# Schematic.net
KiCad netlist of a schematic drawn in EAGLE
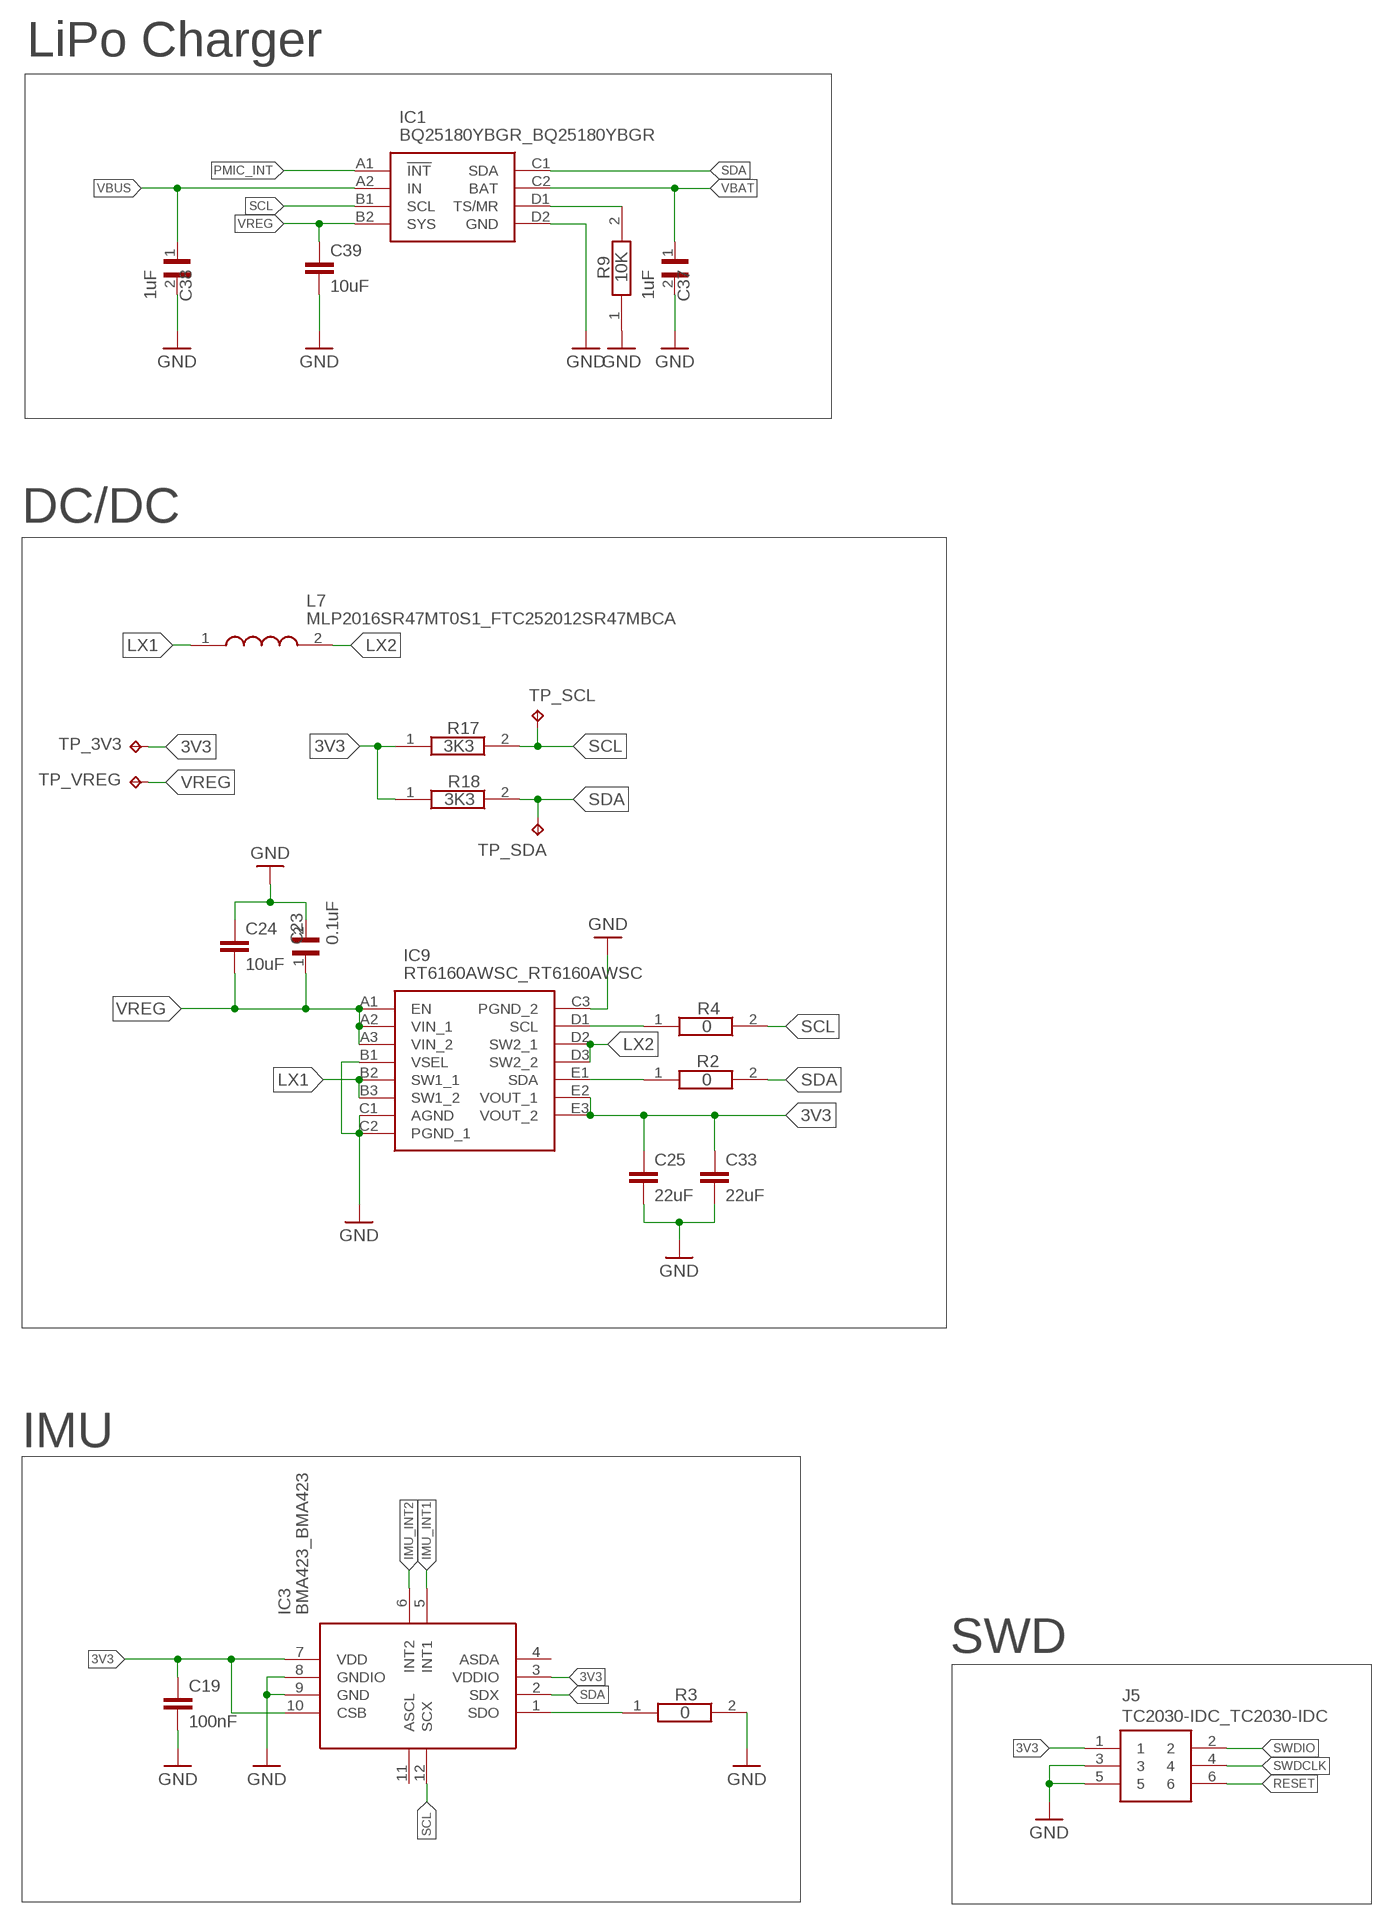
[diagram p0: schematic, sheet 1, part 1 of 3]
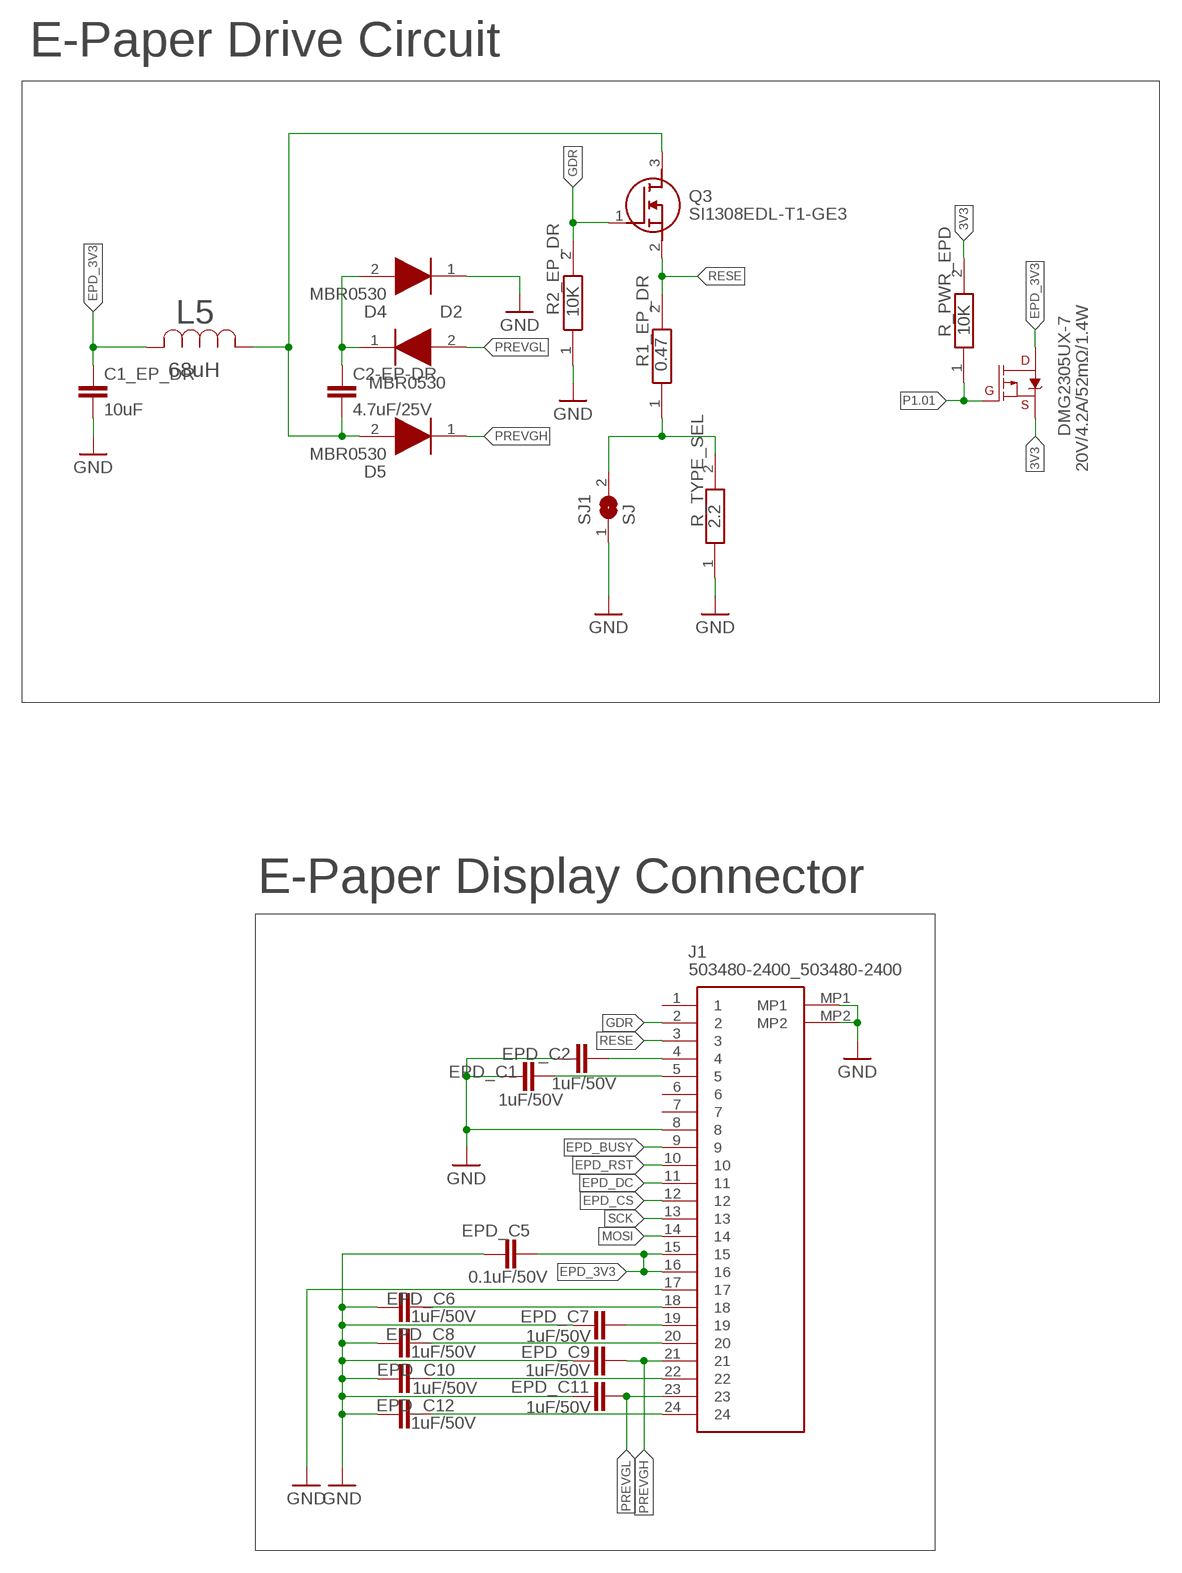
[diagram p1: schematic, sheet 1, part 2 of 3]
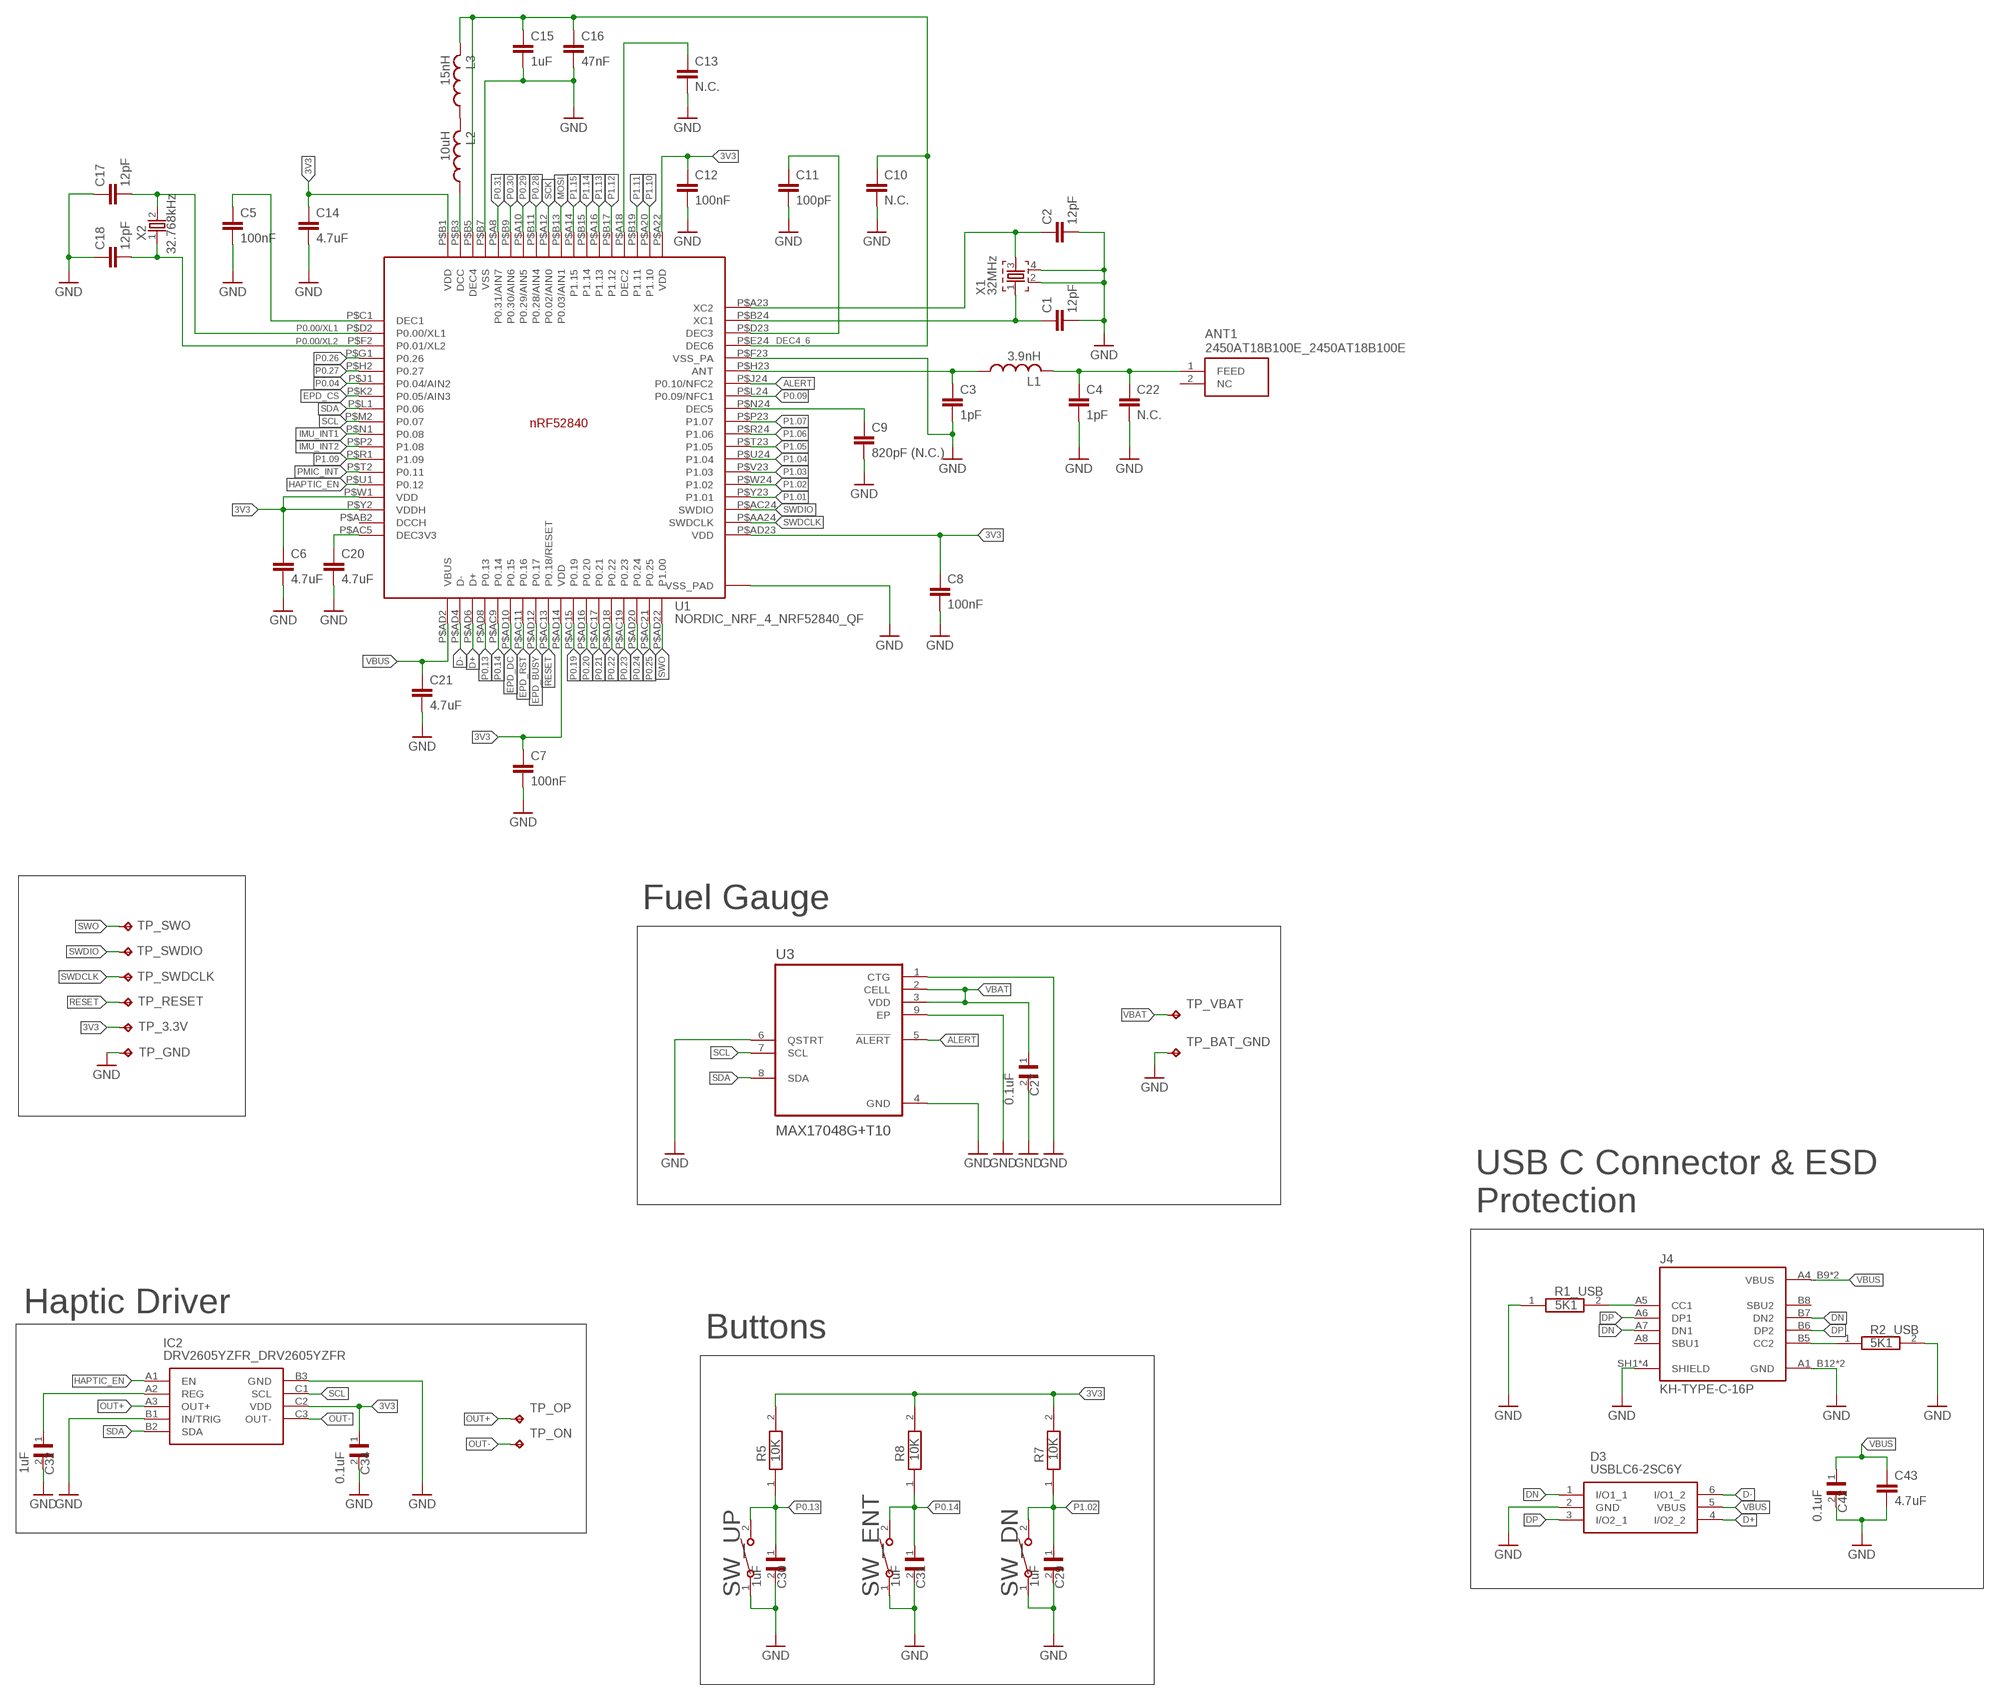
[diagram p2: schematic, sheet 1, part 3 of 3]

(export (version "E")
  (design (tool "Eeschema 10.0.6"))
  (components
    (comp (ref "ANT1")
      (value "2450AT18B100E_2450AT18B100E")
      (footprint "eagle-import:2450AT18B100E_ANTC3216X140N")
      (fields
        (field (name "ARROW_PART_NUMBER") "2450AT18B100E")
        (field (name "MOUSER_PART_NUMBER") "609-2450AT18B100E")
      )
      (libsource (lib "eagle-import") (part "2450AT18B100E_2450AT18B100E"))
    )
    (comp (ref "C1")
      (value "12pF")
      (footprint "eagle-import:NORDIC_NRF_3_RESC0201_L")
      (libsource (lib "eagle-import") (part "NORDIC_NRF_3_CAPACITOR_0201_L"))
    )
    (comp (ref "C1_EP_DR")
      (value "10uF")
      (footprint "eagle-import:NORDIC_NRF_3_RESC0402_L")
      (libsource (lib "eagle-import") (part "NORDIC_NRF_3_CAPACITOR_0402_L"))
    )
    (comp (ref "C2")
      (value "12pF")
      (footprint "eagle-import:NORDIC_NRF_3_RESC0201_L")
      (libsource (lib "eagle-import") (part "NORDIC_NRF_3_CAPACITOR_0201_L"))
    )
    (comp (ref "C2-EP-DR")
      (value "4.7uF/25V")
      (footprint "eagle-import:NORDIC_NRF_3_RESC0402_L")
      (libsource (lib "eagle-import") (part "NORDIC_NRF_3_CAPACITOR_0402_L"))
    )
    (comp (ref "C3")
      (value "1pF")
      (footprint "eagle-import:NORDIC_NRF_3_RESC0201_L")
      (libsource (lib "eagle-import") (part "NORDIC_NRF_3_CAPACITOR_0201_L"))
    )
    (comp (ref "C4")
      (value "1pF")
      (footprint "eagle-import:NORDIC_NRF_3_RESC0201_L")
      (libsource (lib "eagle-import") (part "NORDIC_NRF_3_CAPACITOR_0201_L"))
    )
    (comp (ref "C5")
      (value "100nF")
      (footprint "eagle-import:NORDIC_NRF_3_RESC0201_L")
      (libsource (lib "eagle-import") (part "NORDIC_NRF_3_CAPACITOR_0201_L"))
    )
    (comp (ref "C6")
      (value "4.7uF")
      (footprint "eagle-import:NORDIC_NRF_3_RESC0402_L")
      (libsource (lib "eagle-import") (part "NORDIC_NRF_3_CAPACITOR_0402_L"))
    )
    (comp (ref "C7")
      (value "100nF")
      (footprint "eagle-import:NORDIC_NRF_3_RESC0201_L")
      (libsource (lib "eagle-import") (part "NORDIC_NRF_3_CAPACITOR_0201_L"))
    )
    (comp (ref "C8")
      (value "100nF")
      (footprint "eagle-import:NORDIC_NRF_3_RESC0201_L")
      (libsource (lib "eagle-import") (part "NORDIC_NRF_3_CAPACITOR_0201_L"))
    )
    (comp (ref "C9")
      (value "820pF (N.C.)")
      (footprint "eagle-import:NORDIC_NRF_3_RESC0201_L")
      (libsource (lib "eagle-import") (part "NORDIC_NRF_3_CAPACITOR_0201_L"))
    )
    (comp (ref "C10")
      (value "N.C.")
      (footprint "eagle-import:NORDIC_NRF_3_RESC0201_L")
      (libsource (lib "eagle-import") (part "NORDIC_NRF_3_CAPACITOR_0201_L"))
    )
    (comp (ref "C11")
      (value "100pF")
      (footprint "eagle-import:NORDIC_NRF_3_RESC0201_L")
      (libsource (lib "eagle-import") (part "NORDIC_NRF_3_CAPACITOR_0201_L"))
    )
    (comp (ref "C12")
      (value "100nF")
      (footprint "eagle-import:NORDIC_NRF_3_RESC0201_L")
      (libsource (lib "eagle-import") (part "NORDIC_NRF_3_CAPACITOR_0201_L"))
    )
    (comp (ref "C13")
      (value "N.C.")
      (footprint "eagle-import:NORDIC_NRF_3_RESC0201_L")
      (libsource (lib "eagle-import") (part "NORDIC_NRF_3_CAPACITOR_0201_L"))
    )
    (comp (ref "C14")
      (value "4.7uF")
      (footprint "eagle-import:NORDIC_NRF_3_RESC0402_L")
      (libsource (lib "eagle-import") (part "NORDIC_NRF_3_CAPACITOR_0402_L"))
    )
    (comp (ref "C15")
      (value "1uF")
      (footprint "eagle-import:NORDIC_NRF_3_RESC0402_L")
      (libsource (lib "eagle-import") (part "NORDIC_NRF_3_CAPACITOR_0402_L"))
    )
    (comp (ref "C16")
      (value "47nF")
      (footprint "eagle-import:NORDIC_NRF_3_RESC0201_L")
      (libsource (lib "eagle-import") (part "NORDIC_NRF_3_CAPACITOR_0201_L"))
    )
    (comp (ref "C17")
      (value "12pF")
      (footprint "eagle-import:NORDIC_NRF_3_RESC0201_L")
      (libsource (lib "eagle-import") (part "NORDIC_NRF_3_CAPACITOR_0201_L"))
    )
    (comp (ref "C18")
      (value "12pF")
      (footprint "eagle-import:NORDIC_NRF_3_RESC0201_L")
      (libsource (lib "eagle-import") (part "NORDIC_NRF_3_CAPACITOR_0201_L"))
    )
    (comp (ref "C19")
      (value "100nF")
      (footprint "eagle-import:NORDIC_NRF_3_RESC0201_L")
      (libsource (lib "eagle-import") (part "NORDIC_NRF_3_CAPACITOR_0201_L"))
    )
    (comp (ref "C20")
      (value "4.7uF")
      (footprint "eagle-import:NORDIC_NRF_3_RESC0402_L")
      (libsource (lib "eagle-import") (part "NORDIC_NRF_3_CAPACITOR_0402_L"))
    )
    (comp (ref "C21")
      (value "4.7uF")
      (footprint "eagle-import:NORDIC_NRF_3_RESC0402_L")
      (libsource (lib "eagle-import") (part "NORDIC_NRF_3_CAPACITOR_0402_L"))
    )
    (comp (ref "C22")
      (value "N.C.")
      (footprint "eagle-import:NORDIC_NRF_3_RESC0201_L")
      (libsource (lib "eagle-import") (part "NORDIC_NRF_3_CAPACITOR_0201_L"))
    )
    (comp (ref "C23")
      (value "0.1uF")
      (footprint "eagle-import:GRM011R60J152KE01L_2_CAPC0201X13N")
      (fields (field (name "MF") "Murata") (field (name "MP") "GRM011R60J152KE01L"))
      (libsource (lib "eagle-import") (part "GRM011R60J152KE01L_2_GRM011R60J152KE01L"))
    )
    (comp (ref "C24")
      (value "10uF")
      (footprint "eagle-import:NORDIC_NRF_3_RESC0402_L")
      (libsource (lib "eagle-import") (part "NORDIC_NRF_3_CAPACITOR_0402_L"))
    )
    (comp (ref "C25")
      (value "22uF")
      (footprint "eagle-import:NORDIC_NRF_3_RESC0402_L")
      (libsource (lib "eagle-import") (part "NORDIC_NRF_3_CAPACITOR_0402_L"))
    )
    (comp (ref "C27")
      (value "0.1uF")
      (footprint "eagle-import:GRM011R60J152KE01L_2_CAPC0201X13N")
      (fields (field (name "MF") "Murata") (field (name "MP") "GRM011R60J152KE01L"))
      (libsource (lib "eagle-import") (part "GRM011R60J152KE01L_2_GRM011R60J152KE01L"))
    )
    (comp (ref "C29")
      (value "1uF")
      (footprint "eagle-import:GRM011R60J152KE01L_2_CAPC0201X13N")
      (fields (field (name "MF") "Murata") (field (name "MP") "GRM011R60J152KE01L"))
      (libsource (lib "eagle-import") (part "GRM011R60J152KE01L_2_GRM011R60J152KE01L"))
    )
    (comp (ref "C30")
      (value "1uF")
      (footprint "eagle-import:GRM011R60J152KE01L_2_CAPC0201X13N")
      (fields (field (name "MF") "Murata") (field (name "MP") "GRM011R60J152KE01L"))
      (libsource (lib "eagle-import") (part "GRM011R60J152KE01L_2_GRM011R60J152KE01L"))
    )
    (comp (ref "C31")
      (value "1uF")
      (footprint "eagle-import:GRM011R60J152KE01L_2_CAPC0201X13N")
      (fields (field (name "MF") "Murata") (field (name "MP") "GRM011R60J152KE01L"))
      (libsource (lib "eagle-import") (part "GRM011R60J152KE01L_2_GRM011R60J152KE01L"))
    )
    (comp (ref "C32")
      (value "1uF")
      (footprint "eagle-import:GRM011R60J152KE01L_2_CAPC0201X13N")
      (fields (field (name "MF") "Murata") (field (name "MP") "GRM011R60J152KE01L"))
      (libsource (lib "eagle-import") (part "GRM011R60J152KE01L_2_GRM011R60J152KE01L"))
    )
    (comp (ref "C33")
      (value "22uF")
      (footprint "eagle-import:NORDIC_NRF_3_RESC0402_L")
      (libsource (lib "eagle-import") (part "NORDIC_NRF_3_CAPACITOR_0402_L"))
    )
    (comp (ref "C34")
      (value "0.1uF")
      (footprint "eagle-import:GRM011R60J152KE01L_2_CAPC0201X13N")
      (fields (field (name "MF") "Murata") (field (name "MP") "GRM011R60J152KE01L"))
      (libsource (lib "eagle-import") (part "GRM011R60J152KE01L_2_GRM011R60J152KE01L"))
    )
    (comp (ref "C37")
      (value "1uF")
      (footprint "eagle-import:GRM011R60J152KE01L_2_CAPC0201X13N")
      (fields (field (name "MF") "Murata") (field (name "MP") "GRM011R60J152KE01L"))
      (libsource (lib "eagle-import") (part "GRM011R60J152KE01L_2_GRM011R60J152KE01L"))
    )
    (comp (ref "C38")
      (value "1uF")
      (footprint "eagle-import:GRM011R60J152KE01L_2_CAPC0201X13N")
      (fields (field (name "MF") "Murata") (field (name "MP") "GRM011R60J152KE01L"))
      (libsource (lib "eagle-import") (part "GRM011R60J152KE01L_2_GRM011R60J152KE01L"))
    )
    (comp (ref "C39")
      (value "10uF")
      (footprint "eagle-import:NORDIC_NRF_3_RESC0402_L")
      (libsource (lib "eagle-import") (part "NORDIC_NRF_3_CAPACITOR_0402_L"))
    )
    (comp (ref "C42")
      (value "0.1uF")
      (footprint "eagle-import:GRM011R60J152KE01L_2_CAPC0201X13N")
      (fields (field (name "MF") "Murata") (field (name "MP") "GRM011R60J152KE01L"))
      (libsource (lib "eagle-import") (part "GRM011R60J152KE01L_2_GRM011R60J152KE01L"))
    )
    (comp (ref "C43")
      (value "4.7uF")
      (footprint "eagle-import:NORDIC_NRF_3_RESC0402_L")
      (libsource (lib "eagle-import") (part "NORDIC_NRF_3_CAPACITOR_0402_L"))
    )
    (comp (ref "D2")
      (value "MBR0530")
      (footprint "eagle-import:ESP32_C6_LIBRARY_5_SOD3716X135N")
      (fields (field (name "MF") "ON Semiconductor"))
      (libsource (lib "eagle-import") (part "ESP32_C6_LIBRARY_5_MBR0530"))
    )
    (comp (ref "D3")
      (value "USBLC6-2SC6Y")
      (footprint "eagle-import:ESP32_C6_LIBRARY_3_SOT95P280X145-6N")
      (fields (field (name "MF") "STMicroelectronics"))
      (libsource (lib "eagle-import") (part "ESP32_C6_LIBRARY_3_USBLC6-2SC6Y"))
    )
    (comp (ref "D4")
      (value "MBR0530")
      (footprint "eagle-import:ESP32_C6_LIBRARY_5_SOD3716X135N")
      (fields (field (name "MF") "ON Semiconductor"))
      (libsource (lib "eagle-import") (part "ESP32_C6_LIBRARY_5_MBR0530"))
    )
    (comp (ref "D5")
      (value "MBR0530")
      (footprint "eagle-import:ESP32_C6_LIBRARY_5_SOD3716X135N")
      (fields (field (name "MF") "ON Semiconductor"))
      (libsource (lib "eagle-import") (part "ESP32_C6_LIBRARY_5_MBR0530"))
    )
    (comp (ref "DMG2305UX-7")
      (value "20V/4.2A/52mΩ/1.4W")
      (footprint "eagle-import:ESP32_C6_LIBRARY_4_ESP32_C6_LIBRARY_4_ESP32_C6_LIBRARY_4_ESP32_C6_LIBRARY_4_ESP32_WROVER_SPARKFUN-DISCRETESEMI_SOT23-3")
      (libsource (lib "eagle-import") (part "ESP32_C6_LIBRARY_4_ESP32_WROVER_SPARKFUN-DISCRETESEMI_MOSFET_PCH-DMG2305UX-7"))
    )
    (comp (ref "EPD_C1")
      (value "1uF/50V")
      (footprint "eagle-import:NORDIC_NRF_3_RESC0402_L")
      (libsource (lib "eagle-import") (part "NORDIC_NRF_3_CAPACITOR_0402_L"))
    )
    (comp (ref "EPD_C2")
      (value "1uF/50V")
      (footprint "eagle-import:NORDIC_NRF_3_RESC0402_L")
      (libsource (lib "eagle-import") (part "NORDIC_NRF_3_CAPACITOR_0402_L"))
    )
    (comp (ref "EPD_C5")
      (value "0.1uF/50V")
      (footprint "eagle-import:NORDIC_NRF_3_RESC0201_L")
      (libsource (lib "eagle-import") (part "NORDIC_NRF_3_CAPACITOR_0201_L"))
    )
    (comp (ref "EPD_C6")
      (value "1uF/50V")
      (footprint "eagle-import:NORDIC_NRF_3_RESC0402_L")
      (libsource (lib "eagle-import") (part "NORDIC_NRF_3_CAPACITOR_0402_L"))
    )
    (comp (ref "EPD_C7")
      (value "1uF/50V")
      (footprint "eagle-import:NORDIC_NRF_3_RESC0402_L")
      (libsource (lib "eagle-import") (part "NORDIC_NRF_3_CAPACITOR_0402_L"))
    )
    (comp (ref "EPD_C8")
      (value "1uF/50V")
      (footprint "eagle-import:NORDIC_NRF_3_RESC0402_L")
      (libsource (lib "eagle-import") (part "NORDIC_NRF_3_CAPACITOR_0402_L"))
    )
    (comp (ref "EPD_C9")
      (value "1uF/50V")
      (footprint "eagle-import:NORDIC_NRF_3_RESC0402_L")
      (libsource (lib "eagle-import") (part "NORDIC_NRF_3_CAPACITOR_0402_L"))
    )
    (comp (ref "EPD_C10")
      (value "1uF/50V")
      (footprint "eagle-import:NORDIC_NRF_3_RESC0402_L")
      (libsource (lib "eagle-import") (part "NORDIC_NRF_3_CAPACITOR_0402_L"))
    )
    (comp (ref "EPD_C11")
      (value "1uF/50V")
      (footprint "eagle-import:NORDIC_NRF_3_RESC0402_L")
      (libsource (lib "eagle-import") (part "NORDIC_NRF_3_CAPACITOR_0402_L"))
    )
    (comp (ref "EPD_C12")
      (value "1uF/50V")
      (footprint "eagle-import:NORDIC_NRF_3_RESC0402_L")
      (libsource (lib "eagle-import") (part "NORDIC_NRF_3_CAPACITOR_0402_L"))
    )
    (comp (ref "IC1")
      (value "BQ25180YBGR_BQ25180YBGR")
      (footprint "eagle-import:BQ25180YBGR_BGA8C40P2X4_100X155X50")
      (fields
        (field (name "ARROW_PART_NUMBER") "BQ25180YBGR")
        (field (name "MOUSER_PART_NUMBER") "595-BQ25180YBGR")
      )
      (libsource (lib "eagle-import") (part "BQ25180YBGR_BQ25180YBGR"))
    )
    (comp (ref "IC2")
      (value "DRV2605YZFR_DRV2605YZFR")
      (footprint "eagle-import:DRV2605YZFR_BGA9C50P3X3_144X144X62")
      (fields (field (name "ARROW_PART_NUMBER") "DRV2605YZFR"))
      (libsource (lib "eagle-import") (part "DRV2605YZFR_DRV2605YZFR"))
    )
    (comp (ref "IC3")
      (value "BMA423_BMA423")
      (footprint "eagle-import:BMA423_BMA423")
      (fields (field (name "ARROW_PART_NUMBER") "BMA423") (field (name "MOUSER_PART_NUMBER") "262-BMA423"))
      (libsource (lib "eagle-import") (part "BMA423_BMA423"))
    )
    (comp (ref "IC9")
      (value "RT6160AWSC_RT6160AWSC")
      (footprint "eagle-import:RT6160AWSC_BGA15C40P3X5_140X230X60")
      (fields
        (field (name "MANUFACTURER_PART_NUMBER") "RT6160AWSC")
        (field (name "MOUSER_PART_NUMBER") "835-RT6160AWSC")
      )
      (libsource (lib "eagle-import") (part "RT6160AWSC_RT6160AWSC"))
    )
    (comp (ref "J1")
      (value "503480-2400_503480-2400")
      (footprint "eagle-import:503480-2400_5034802400")
      (fields
        (field (name "MANUFACTURER_PART_NUMBER") "503480-2400")
        (field (name "MOUSER_PART_NUMBER") "538-503480-2400")
      )
      (libsource (lib "eagle-import") (part "503480-2400_503480-2400"))
    )
    (comp (ref "J4")
      (value "KH-TYPE-C-16P")
      (footprint "eagle-import:KH-TYPE-C-16P_KINGHELM_KH-TYPE-C-16P")
      (fields (field (name "MF") "kinghelm"))
      (libsource (lib "eagle-import") (part "KH-TYPE-C-16P_KH-TYPE-C-16P"))
    )
    (comp (ref "J5")
      (value "TC2030-IDC_TC2030-IDC")
      (footprint "eagle-import:TC2030-IDC_TC2030IDC")
      (fields (field (name "MANUFACTURER_PART_NUMBER") "TC2030-IDC"))
      (libsource (lib "eagle-import") (part "TC2030-IDC_TC2030-IDC"))
    )
    (comp (ref "L1")
      (value "3.9nH")
      (footprint "eagle-import:NORDIC_NRF_2_RESC0201_L")
      (libsource (lib "eagle-import") (part "NORDIC_NRF_2_INDUCTOR_0201_L"))
    )
    (comp (ref "L2")
      (value "10uH")
      (footprint "eagle-import:NORDIC_NRF_2_RESC0402_L")
      (libsource (lib "eagle-import") (part "NORDIC_NRF_2_INDUCTOR_0402_L"))
    )
    (comp (ref "L3")
      (value "15nH")
      (footprint "eagle-import:NORDIC_NRF_2_RESC0201_L")
      (libsource (lib "eagle-import") (part "NORDIC_NRF_2_INDUCTOR_0201_L"))
    )
    (comp (ref "L5")
      (value "68uH")
      (footprint "eagle-import:ESP32_C6_LIBRARY_2_IND_4828-WE-TPC_WRE")
      (fields
        (field (name "MANUFACTURER_PART_NUMBER") "744043680")
        (field (name "COPYRIGHT") "Copyright (C) 2024 Ultra Librarian. All rights reserved.")
      )
      (libsource (lib "eagle-import") (part "ESP32_C6_LIBRARY_2_744043680IND_4828-WE-TPC_WRE"))
    )
    (comp (ref "L7")
      (value "MLP2016SR47MT0S1_FTC252012SR47MBCA")
      (footprint "eagle-import:MLP2016SR47MT0S1_INDC2016X100N")
      (fields (field (name "MANUFACTURER_PART_NUMBER") "FTC252012SR47MBCA"))
      (libsource (lib "eagle-import") (part "MLP2016SR47MT0S1_FTC252012SR47MBCA"))
    )
    (comp (ref "Q3")
      (value "SI1308EDL-T1-GE3")
      (footprint "eagle-import:ESP32_C6_LIBRARY_6_SOT65P210X110-3N")
      (fields (field (name "MF") "Vishay Siliconix"))
      (libsource (lib "eagle-import") (part "ESP32_C6_LIBRARY_6_SI1308EDL-T1-GE3"))
    )
    (comp (ref "R1_EP_DR")
      (value "0.47")
      (footprint "eagle-import:CPF0201D7K68C1_0201")
      (libsource (lib "eagle-import") (part "CPF0201D7K68C1_CPF0201D7K68C1"))
    )
    (comp (ref "R1_USB")
      (value "5K1")
      (footprint "eagle-import:CPF0201D7K68C1_0201")
      (libsource (lib "eagle-import") (part "CPF0201D7K68C1_CPF0201D7K68C1"))
    )
    (comp (ref "R2")
      (value "0")
      (footprint "eagle-import:CPF0201D7K68C1_0201")
      (libsource (lib "eagle-import") (part "CPF0201D7K68C1_CPF0201D7K68C1"))
    )
    (comp (ref "R2_EP_DR")
      (value "10K")
      (footprint "eagle-import:CPF0201D7K68C1_0201")
      (libsource (lib "eagle-import") (part "CPF0201D7K68C1_CPF0201D7K68C1"))
    )
    (comp (ref "R2_USB")
      (value "5K1")
      (footprint "eagle-import:CPF0201D7K68C1_0201")
      (libsource (lib "eagle-import") (part "CPF0201D7K68C1_CPF0201D7K68C1"))
    )
    (comp (ref "R3")
      (value "0")
      (footprint "eagle-import:CPF0201D7K68C1_0201")
      (libsource (lib "eagle-import") (part "CPF0201D7K68C1_CPF0201D7K68C1"))
    )
    (comp (ref "R4")
      (value "0")
      (footprint "eagle-import:CPF0201D7K68C1_0201")
      (libsource (lib "eagle-import") (part "CPF0201D7K68C1_CPF0201D7K68C1"))
    )
    (comp (ref "R5")
      (value "10K")
      (footprint "eagle-import:CPF0201D7K68C1_0201")
      (libsource (lib "eagle-import") (part "CPF0201D7K68C1_CPF0201D7K68C1"))
    )
    (comp (ref "R7")
      (value "10K")
      (footprint "eagle-import:CPF0201D7K68C1_0201")
      (libsource (lib "eagle-import") (part "CPF0201D7K68C1_CPF0201D7K68C1"))
    )
    (comp (ref "R8")
      (value "10K")
      (footprint "eagle-import:CPF0201D7K68C1_0201")
      (libsource (lib "eagle-import") (part "CPF0201D7K68C1_CPF0201D7K68C1"))
    )
    (comp (ref "R9")
      (value "10K")
      (footprint "eagle-import:CPF0201D7K68C1_0201")
      (libsource (lib "eagle-import") (part "CPF0201D7K68C1_CPF0201D7K68C1"))
    )
    (comp (ref "R17")
      (value "3K3")
      (footprint "eagle-import:CPF0201D7K68C1_0201")
      (libsource (lib "eagle-import") (part "CPF0201D7K68C1_CPF0201D7K68C1"))
    )
    (comp (ref "R18")
      (value "3K3")
      (footprint "eagle-import:CPF0201D7K68C1_0201")
      (libsource (lib "eagle-import") (part "CPF0201D7K68C1_CPF0201D7K68C1"))
    )
    (comp (ref "R_PWR_EPD")
      (value "10K")
      (footprint "eagle-import:CPF0201D7K68C1_0201")
      (libsource (lib "eagle-import") (part "CPF0201D7K68C1_CPF0201D7K68C1"))
    )
    (comp (ref "R_TYPE_SEL")
      (value "2.2")
      (footprint "eagle-import:CPF0201D7K68C1_0201")
      (libsource (lib "eagle-import") (part "CPF0201D7K68C1_CPF0201D7K68C1"))
    )
    (comp (ref "SJ1")
      (value "SJ")
      (footprint "eagle-import:ESP32_C6_LIBRARY_7_JUMPER_SJ")
      (libsource (lib "eagle-import") (part "ESP32_C6_LIBRARY_7_JUMPER_SJ"))
    )
    (comp (ref "SW_DN")
      (value "2025-10-22_07-23-44_LIBRARY_EVP-AKE31ASW_EVP-AKE31A_PAN")
      (footprint "eagle-import:2025-10-22_07-23-44_LIBRARY_SW_EVP-AKE31A_PAN")
      (fields
        (field (name "MANUFACTURER_PART_NUMBER") "EVP-AKE31A")
        (field (name "COPYRIGHT") "Copyright (C) 2025 Ultra Librarian. All rights reserved.")
      )
      (libsource (lib "eagle-import") (part "2025-10-22_07-23-44_LIBRARY_EVP-AKE31ASW_EVP-AKE31A_PAN"))
    )
    (comp (ref "SW_ENT")
      (value "2025-10-22_07-23-44_LIBRARY_EVP-AKE31ASW_EVP-AKE31A_PAN")
      (footprint "eagle-import:2025-10-22_07-23-44_LIBRARY_SW_EVP-AKE31A_PAN")
      (fields
        (field (name "MANUFACTURER_PART_NUMBER") "EVP-AKE31A")
        (field (name "COPYRIGHT") "Copyright (C) 2025 Ultra Librarian. All rights reserved.")
      )
      (libsource (lib "eagle-import") (part "2025-10-22_07-23-44_LIBRARY_EVP-AKE31ASW_EVP-AKE31A_PAN"))
    )
    (comp (ref "SW_UP")
      (value "2025-10-22_07-23-44_LIBRARY_EVP-AKE31ASW_EVP-AKE31A_PAN")
      (footprint "eagle-import:2025-10-22_07-23-44_LIBRARY_SW_EVP-AKE31A_PAN")
      (fields
        (field (name "MANUFACTURER_PART_NUMBER") "EVP-AKE31A")
        (field (name "COPYRIGHT") "Copyright (C) 2025 Ultra Librarian. All rights reserved.")
      )
      (libsource (lib "eagle-import") (part "2025-10-22_07-23-44_LIBRARY_EVP-AKE31ASW_EVP-AKE31A_PAN"))
    )
    (comp (ref "TP_3.3V")
      (value "HECTOR_WATCH_1_TPTP20R")
      (footprint "eagle-import:HECTOR_WATCH_1_TP20R")
      (libsource (lib "eagle-import") (part "HECTOR_WATCH_1_TPTP20R"))
    )
    (comp (ref "TP_3V3")
      (value "HECTOR_WATCH_1_TPTP20R")
      (footprint "eagle-import:HECTOR_WATCH_1_TP20R")
      (libsource (lib "eagle-import") (part "HECTOR_WATCH_1_TPTP20R"))
    )
    (comp (ref "TP_BAT_GND")
      (value "HECTOR_WATCH_1_TPTP20R")
      (footprint "eagle-import:HECTOR_WATCH_1_TP20R")
      (libsource (lib "eagle-import") (part "HECTOR_WATCH_1_TPTP20R"))
    )
    (comp (ref "TP_GND")
      (value "HECTOR_WATCH_1_TPTP20R")
      (footprint "eagle-import:HECTOR_WATCH_1_TP20R")
      (libsource (lib "eagle-import") (part "HECTOR_WATCH_1_TPTP20R"))
    )
    (comp (ref "TP_ON")
      (value "HECTOR_WATCH_1_TPTP20R")
      (footprint "eagle-import:HECTOR_WATCH_1_TP20R")
      (libsource (lib "eagle-import") (part "HECTOR_WATCH_1_TPTP20R"))
    )
    (comp (ref "TP_OP")
      (value "HECTOR_WATCH_1_TPTP20R")
      (footprint "eagle-import:HECTOR_WATCH_1_TP20R")
      (libsource (lib "eagle-import") (part "HECTOR_WATCH_1_TPTP20R"))
    )
    (comp (ref "TP_RESET")
      (value "HECTOR_WATCH_1_TPTP20R")
      (footprint "eagle-import:HECTOR_WATCH_1_TP20R")
      (libsource (lib "eagle-import") (part "HECTOR_WATCH_1_TPTP20R"))
    )
    (comp (ref "TP_SCL")
      (value "HECTOR_WATCH_1_TPTP20R")
      (footprint "eagle-import:HECTOR_WATCH_1_TP20R")
      (libsource (lib "eagle-import") (part "HECTOR_WATCH_1_TPTP20R"))
    )
    (comp (ref "TP_SDA")
      (value "HECTOR_WATCH_1_TPTP20R")
      (footprint "eagle-import:HECTOR_WATCH_1_TP20R")
      (libsource (lib "eagle-import") (part "HECTOR_WATCH_1_TPTP20R"))
    )
    (comp (ref "TP_SWDCLK")
      (value "HECTOR_WATCH_1_TPTP20R")
      (footprint "eagle-import:HECTOR_WATCH_1_TP20R")
      (libsource (lib "eagle-import") (part "HECTOR_WATCH_1_TPTP20R"))
    )
    (comp (ref "TP_SWDIO")
      (value "HECTOR_WATCH_1_TPTP20R")
      (footprint "eagle-import:HECTOR_WATCH_1_TP20R")
      (libsource (lib "eagle-import") (part "HECTOR_WATCH_1_TPTP20R"))
    )
    (comp (ref "TP_SWO")
      (value "HECTOR_WATCH_1_TPTP20R")
      (footprint "eagle-import:HECTOR_WATCH_1_TP20R")
      (libsource (lib "eagle-import") (part "HECTOR_WATCH_1_TPTP20R"))
    )
    (comp (ref "TP_VBAT")
      (value "HECTOR_WATCH_1_TPTP20R")
      (footprint "eagle-import:HECTOR_WATCH_1_TP20R")
      (libsource (lib "eagle-import") (part "HECTOR_WATCH_1_TPTP20R"))
    )
    (comp (ref "TP_VREG")
      (value "HECTOR_WATCH_1_TPTP20R")
      (footprint "eagle-import:HECTOR_WATCH_1_TP20R")
      (libsource (lib "eagle-import") (part "HECTOR_WATCH_1_TPTP20R"))
    )
    (comp (ref "U1")
      (value "NORDIC_NRF_4_NRF52840_QF")
      (footprint "eagle-import:NORDIC_NRF_4_AQFN50P700X700X85_HS-74N")
      (libsource (lib "eagle-import") (part "NORDIC_NRF_4_NRF52840_QF"))
    )
    (comp (ref "U3")
      (value "MAX17048G+T10")
      (footprint "eagle-import:ESP32_C6_LIBRARY_SON50P200X200X80-9N")
      (fields (field (name "MF") "Analog Devices"))
      (libsource (lib "eagle-import") (part "ESP32_C6_LIBRARY_MAX17048G+T10"))
    )
    (comp (ref "X1")
      (value "32MHz")
      (footprint "eagle-import:NORDIC_NRF_BT-XTAL_2016_N")
      (libsource (lib "eagle-import") (part "NORDIC_NRF_XTAL_32MHZ"))
    )
    (comp (ref "X2")
      (value "32.768kHz")
      (footprint "eagle-import:NORDIC_NRF_1_XTAL_3215_N")
      (libsource (lib "eagle-import") (part "NORDIC_NRF_1_XTAL_32KHZ"))
    )
  )
  (nets
    (net (code "1") (name "/DEC4_6") (class "Default")
      (node (ref "C10") (pin "1") (pinfunction "1_1") (pintype "passive"))
      (node (ref "C15") (pin "1") (pinfunction "1_1") (pintype "passive"))
      (node (ref "C16") (pin "1") (pinfunction "1_1") (pintype "passive"))
      (node (ref "L3") (pin "2") (pinfunction "2_2") (pintype "passive"))
      (node (ref "U1") (pin "P$B5") (pinfunction "DEC4_P$B5") (pintype "power_in"))
      (node (ref "U1") (pin "P$E24") (pinfunction "DEC6_P$E24") (pintype "bidirectional"))
    )
    (net (code "2") (name "/P0.00{slash}XL1") (class "Default")
      (node (ref "C17") (pin "2") (pinfunction "2_2") (pintype "passive"))
      (node (ref "U1") (pin "P$D2") (pinfunction "P0.00/XL1_P$D2") (pintype "bidirectional"))
      (node (ref "X2") (pin "2") (pinfunction "2_2") (pintype "passive"))
    )
    (net (code "3") (name "/P0.00{slash}XL2") (class "Default")
      (node (ref "C18") (pin "2") (pinfunction "2_2") (pintype "passive"))
      (node (ref "U1") (pin "P$F2") (pinfunction "P0.01/XL2_P$F2") (pintype "bidirectional"))
      (node (ref "X2") (pin "1") (pinfunction "1_1") (pintype "passive"))
    )
    (net (code "4") (name "3V3") (class "Default")
      (node (ref "C12") (pin "1") (pinfunction "1_1") (pintype "passive"))
      (node (ref "C14") (pin "1") (pinfunction "1_1") (pintype "passive"))
      (node (ref "C19") (pin "1") (pinfunction "1_1") (pintype "passive"))
      (node (ref "C25") (pin "1") (pinfunction "1_1") (pintype "passive"))
      (node (ref "C33") (pin "1") (pinfunction "1_1") (pintype "passive"))
      (node (ref "C34") (pin "1") (pinfunction "1_1") (pintype "passive"))
      (node (ref "C6") (pin "1") (pinfunction "1_1") (pintype "passive"))
      (node (ref "C7") (pin "1") (pinfunction "1_1") (pintype "passive"))
      (node (ref "C8") (pin "1") (pinfunction "1_1") (pintype "passive"))
      (node (ref "DMG2305UX-7") (pin "2") (pinfunction "S_2") (pintype "bidirectional"))
      (node (ref "IC2") (pin "C2") (pinfunction "VDD_C2") (pintype "bidirectional"))
      (node (ref "IC3") (pin "10") (pinfunction "CSB_10") (pintype "bidirectional"))
      (node (ref "IC3") (pin "3") (pinfunction "VDDIO_3") (pintype "bidirectional"))
      (node (ref "IC3") (pin "7") (pinfunction "VDD_7") (pintype "bidirectional"))
      (node (ref "IC9") (pin "E2") (pinfunction "VOUT_1_E2") (pintype "bidirectional"))
      (node (ref "IC9") (pin "E3") (pinfunction "VOUT_2_E3") (pintype "bidirectional"))
      (node (ref "J5") (pin "1") (pinfunction "1_1") (pintype "bidirectional"))
      (node (ref "R17") (pin "1") (pinfunction "1_1") (pintype "bidirectional"))
      (node (ref "R18") (pin "1") (pinfunction "1_1") (pintype "bidirectional"))
      (node (ref "R5") (pin "2") (pinfunction "2_2") (pintype "bidirectional"))
      (node (ref "R7") (pin "2") (pinfunction "2_2") (pintype "bidirectional"))
      (node (ref "R8") (pin "2") (pinfunction "2_2") (pintype "bidirectional"))
      (node (ref "R_PWR_EPD") (pin "2") (pinfunction "2_2") (pintype "bidirectional"))
      (node (ref "TP_3.3V") (pin "TP") (pinfunction "TP_TP") (pintype "input"))
      (node (ref "TP_3V3") (pin "TP") (pinfunction "TP_TP") (pintype "input"))
      (node (ref "U1") (pin "P$A22") (pinfunction "VDD_P$A22") (pintype "power_in"))
      (node (ref "U1") (pin "P$AD14") (pinfunction "VDD_P$AD14") (pintype "power_in"))
      (node (ref "U1") (pin "P$AD23") (pinfunction "VDD_P$AD23") (pintype "power_in"))
      (node (ref "U1") (pin "P$B1") (pinfunction "VDD_P$B1") (pintype "power_in"))
      (node (ref "U1") (pin "P$W1") (pinfunction "VDD_P$W1") (pintype "power_in"))
      (node (ref "U1") (pin "P$Y2") (pinfunction "VDDH_P$Y2") (pintype "power_in"))
    )
    (net (code "5") (name "ALERT") (class "Default")
      (node (ref "U1") (pin "P$J24") (pinfunction "P0.10/NFC2_P$J24") (pintype "bidirectional"))
      (node (ref "U3") (pin "5") (pinfunction "~{ALERT}_5") (pintype "output"))
    )
    (net (code "6") (name "D+") (class "Default")
      (node (ref "D3") (pin "4") (pinfunction "I/O2_2_4") (pintype "bidirectional"))
      (node (ref "U1") (pin "P$AD6") (pinfunction "D+_P$AD6") (pintype "bidirectional"))
    )
    (net (code "7") (name "D-") (class "Default")
      (node (ref "D3") (pin "6") (pinfunction "I/O1_2_6") (pintype "bidirectional"))
      (node (ref "U1") (pin "P$AD4") (pinfunction "D-_P$AD4") (pintype "bidirectional"))
    )
    (net (code "8") (name "DN") (class "Default")
      (node (ref "D3") (pin "1") (pinfunction "I/O1_1_1") (pintype "bidirectional"))
      (node (ref "J4") (pin "A7") (pinfunction "DN1_A7") (pintype "bidirectional"))
      (node (ref "J4") (pin "B7") (pinfunction "DN2_B7") (pintype "bidirectional"))
    )
    (net (code "9") (name "DP") (class "Default")
      (node (ref "D3") (pin "3") (pinfunction "I/O2_1_3") (pintype "bidirectional"))
      (node (ref "J4") (pin "A6") (pinfunction "DP1_A6") (pintype "bidirectional"))
      (node (ref "J4") (pin "B6") (pinfunction "DP2_B6") (pintype "bidirectional"))
    )
    (net (code "10") (name "EPD_3V3") (class "Default")
      (node (ref "C1_EP_DR") (pin "1") (pinfunction "1_1") (pintype "passive"))
      (node (ref "DMG2305UX-7") (pin "3") (pinfunction "D_3") (pintype "bidirectional"))
      (node (ref "EPD_C5") (pin "2") (pinfunction "2_2") (pintype "passive"))
      (node (ref "J1") (pin "15") (pinfunction "15_15") (pintype "bidirectional"))
      (node (ref "J1") (pin "16") (pinfunction "16_16") (pintype "bidirectional"))
      (node (ref "L5") (pin "2") (pinfunction "2_2") (pintype "passive"))
    )
    (net (code "11") (name "EPD_BUSY") (class "Default")
      (node (ref "J1") (pin "9") (pinfunction "9_9") (pintype "bidirectional"))
      (node (ref "U1") (pin "P$AD12") (pinfunction "P0.17_P$AD12") (pintype "bidirectional"))
    )
    (net (code "12") (name "EPD_CS") (class "Default")
      (node (ref "J1") (pin "12") (pinfunction "12_12") (pintype "bidirectional"))
      (node (ref "U1") (pin "P$K2") (pinfunction "P0.05/AIN3_P$K2") (pintype "bidirectional"))
    )
    (net (code "13") (name "EPD_DC") (class "Default")
      (node (ref "J1") (pin "11") (pinfunction "11_11") (pintype "bidirectional"))
      (node (ref "U1") (pin "P$AD10") (pinfunction "P0.15_P$AD10") (pintype "bidirectional"))
    )
    (net (code "14") (name "EPD_RST") (class "Default")
      (node (ref "J1") (pin "10") (pinfunction "10_10") (pintype "bidirectional"))
      (node (ref "U1") (pin "P$AC11") (pinfunction "P0.16_P$AC11") (pintype "bidirectional"))
    )
    (net (code "15") (name "GDR") (class "Default")
      (node (ref "J1") (pin "2") (pinfunction "2_2") (pintype "bidirectional"))
      (node (ref "Q3") (pin "1") (pinfunction "G_1") (pintype "bidirectional"))
      (node (ref "R2_EP_DR") (pin "2") (pinfunction "2_2") (pintype "bidirectional"))
    )
    (net (code "16") (name "GND") (class "Default")
      (node (ref "C1") (pin "2") (pinfunction "2_2") (pintype "passive"))
      (node (ref "C10") (pin "2") (pinfunction "2_2") (pintype "passive"))
      (node (ref "C11") (pin "2") (pinfunction "2_2") (pintype "passive"))
      (node (ref "C12") (pin "2") (pinfunction "2_2") (pintype "passive"))
      (node (ref "C13") (pin "2") (pinfunction "2_2") (pintype "passive"))
      (node (ref "C14") (pin "2") (pinfunction "2_2") (pintype "passive"))
      (node (ref "C15") (pin "2") (pinfunction "2_2") (pintype "passive"))
      (node (ref "C16") (pin "2") (pinfunction "2_2") (pintype "passive"))
      (node (ref "C17") (pin "1") (pinfunction "1_1") (pintype "passive"))
      (node (ref "C18") (pin "1") (pinfunction "1_1") (pintype "passive"))
      (node (ref "C19") (pin "2") (pinfunction "2_2") (pintype "passive"))
      (node (ref "C1_EP_DR") (pin "2") (pinfunction "2_2") (pintype "passive"))
      (node (ref "C2") (pin "2") (pinfunction "2_2") (pintype "passive"))
      (node (ref "C20") (pin "2") (pinfunction "2_2") (pintype "passive"))
      (node (ref "C21") (pin "2") (pinfunction "2_2") (pintype "passive"))
      (node (ref "C22") (pin "2") (pinfunction "2_2") (pintype "passive"))
      (node (ref "C23") (pin "2") (pinfunction "2_2") (pintype "passive"))
      (node (ref "C24") (pin "1") (pinfunction "1_1") (pintype "passive"))
      (node (ref "C25") (pin "2") (pinfunction "2_2") (pintype "passive"))
      (node (ref "C27") (pin "2") (pinfunction "2_2") (pintype "passive"))
      (node (ref "C29") (pin "2") (pinfunction "2_2") (pintype "passive"))
      (node (ref "C3") (pin "2") (pinfunction "2_2") (pintype "passive"))
      (node (ref "C30") (pin "2") (pinfunction "2_2") (pintype "passive"))
      (node (ref "C31") (pin "2") (pinfunction "2_2") (pintype "passive"))
      (node (ref "C32") (pin "2") (pinfunction "2_2") (pintype "passive"))
      (node (ref "C33") (pin "2") (pinfunction "2_2") (pintype "passive"))
      (node (ref "C34") (pin "2") (pinfunction "2_2") (pintype "passive"))
      (node (ref "C37") (pin "2") (pinfunction "2_2") (pintype "passive"))
      (node (ref "C38") (pin "2") (pinfunction "2_2") (pintype "passive"))
      (node (ref "C39") (pin "2") (pinfunction "2_2") (pintype "passive"))
      (node (ref "C4") (pin "2") (pinfunction "2_2") (pintype "passive"))
      (node (ref "C42") (pin "2") (pinfunction "2_2") (pintype "passive"))
      (node (ref "C43") (pin "2") (pinfunction "2_2") (pintype "passive"))
      (node (ref "C5") (pin "2") (pinfunction "2_2") (pintype "passive"))
      (node (ref "C6") (pin "2") (pinfunction "2_2") (pintype "passive"))
      (node (ref "C7") (pin "2") (pinfunction "2_2") (pintype "passive"))
      (node (ref "C8") (pin "2") (pinfunction "2_2") (pintype "passive"))
      (node (ref "C9") (pin "2") (pinfunction "2_2") (pintype "passive"))
      (node (ref "D3") (pin "2") (pinfunction "GND_2") (pintype "bidirectional"))
      (node (ref "D4") (pin "1") (pinfunction "K_1") (pintype "bidirectional"))
      (node (ref "EPD_C1") (pin "1") (pinfunction "1_1") (pintype "passive"))
      (node (ref "EPD_C10") (pin "1") (pinfunction "1_1") (pintype "passive"))
      (node (ref "EPD_C11") (pin "1") (pinfunction "1_1") (pintype "passive"))
      (node (ref "EPD_C12") (pin "1") (pinfunction "1_1") (pintype "passive"))
      (node (ref "EPD_C2") (pin "1") (pinfunction "1_1") (pintype "passive"))
      (node (ref "EPD_C5") (pin "1") (pinfunction "1_1") (pintype "passive"))
      (node (ref "EPD_C6") (pin "1") (pinfunction "1_1") (pintype "passive"))
      (node (ref "EPD_C7") (pin "1") (pinfunction "1_1") (pintype "passive"))
      (node (ref "EPD_C8") (pin "1") (pinfunction "1_1") (pintype "passive"))
      (node (ref "EPD_C9") (pin "1") (pinfunction "1_1") (pintype "passive"))
      (node (ref "IC1") (pin "D2") (pinfunction "GND_D2") (pintype "bidirectional"))
      (node (ref "IC2") (pin "B1") (pinfunction "IN/TRIG_B1") (pintype "bidirectional"))
      (node (ref "IC2") (pin "B3") (pinfunction "GND_B3") (pintype "bidirectional"))
      (node (ref "IC3") (pin "8") (pinfunction "GNDIO_8") (pintype "bidirectional"))
      (node (ref "IC3") (pin "9") (pinfunction "GND_9") (pintype "bidirectional"))
      (node (ref "IC9") (pin "B1") (pinfunction "VSEL_B1") (pintype "bidirectional"))
      (node (ref "IC9") (pin "C1") (pinfunction "AGND_C1") (pintype "bidirectional"))
      (node (ref "IC9") (pin "C2") (pinfunction "PGND_1_C2") (pintype "bidirectional"))
      (node (ref "IC9") (pin "C3") (pinfunction "PGND_2_C3") (pintype "bidirectional"))
      (node (ref "J1") (pin "17") (pinfunction "17_17") (pintype "bidirectional"))
      (node (ref "J1") (pin "8") (pinfunction "8_8") (pintype "bidirectional"))
      (node (ref "J1") (pin "MP1") (pinfunction "MP1_MP1") (pintype "bidirectional"))
      (node (ref "J1") (pin "MP2") (pinfunction "MP2_MP2") (pintype "bidirectional"))
      (node (ref "J4") (pin "A12_B1") (pinfunction "GND_A12_B1") (pintype "power_in"))
      (node (ref "J4") (pin "A1_B12") (pinfunction "GND_A1_B12") (pintype "power_in"))
      (node (ref "J4") (pin "SH1") (pinfunction "SHIELD_SH1") (pintype "passive"))
      (node (ref "J4") (pin "SH2") (pinfunction "SHIELD_SH2") (pintype "passive"))
      (node (ref "J4") (pin "SH3") (pinfunction "SHIELD_SH3") (pintype "passive"))
      (node (ref "J4") (pin "SH4") (pinfunction "SHIELD_SH4") (pintype "passive"))
      (node (ref "J5") (pin "3") (pinfunction "3_3") (pintype "bidirectional"))
      (node (ref "J5") (pin "5") (pinfunction "5_5") (pintype "bidirectional"))
      (node (ref "R1_USB") (pin "1") (pinfunction "1_1") (pintype "bidirectional"))
      (node (ref "R2_EP_DR") (pin "1") (pinfunction "1_1") (pintype "bidirectional"))
      (node (ref "R2_USB") (pin "2") (pinfunction "2_2") (pintype "bidirectional"))
      (node (ref "R3") (pin "2") (pinfunction "2_2") (pintype "bidirectional"))
      (node (ref "R9") (pin "1") (pinfunction "1_1") (pintype "bidirectional"))
      (node (ref "R_TYPE_SEL") (pin "1") (pinfunction "1_1") (pintype "bidirectional"))
      (node (ref "SJ1") (pin "1") (pinfunction "1_1") (pintype "passive"))
      (node (ref "SW_DN") (pin "1") (pinfunction "1_1") (pintype "passive"))
      (node (ref "SW_ENT") (pin "1") (pinfunction "1_1") (pintype "passive"))
      (node (ref "SW_UP") (pin "1") (pinfunction "1_1") (pintype "passive"))
      (node (ref "TP_BAT_GND") (pin "TP") (pinfunction "TP_TP") (pintype "input"))
      (node (ref "TP_GND") (pin "TP") (pinfunction "TP_TP") (pintype "input"))
      (node (ref "U1") (pin "P$74") (pinfunction "VSS_PAD_P$74") (pintype "bidirectional"))
      (node (ref "U1") (pin "P$75") (pinfunction "VSS_PAD_P$75") (pintype "bidirectional"))
      (node (ref "U1") (pin "P$76") (pinfunction "VSS_PAD_P$76") (pintype "bidirectional"))
      (node (ref "U1") (pin "P$77") (pinfunction "VSS_PAD_P$77") (pintype "bidirectional"))
      (node (ref "U1") (pin "P$78") (pinfunction "VSS_PAD_P$78") (pintype "bidirectional"))
      (node (ref "U1") (pin "P$79") (pinfunction "VSS_PAD_P$79") (pintype "bidirectional"))
      (node (ref "U1") (pin "P$80") (pinfunction "VSS_PAD_P$80") (pintype "bidirectional"))
      (node (ref "U1") (pin "P$81") (pinfunction "VSS_PAD_P$81") (pintype "bidirectional"))
      (node (ref "U1") (pin "P$82") (pinfunction "VSS_PAD_P$82") (pintype "bidirectional"))
      (node (ref "U1") (pin "P$83") (pinfunction "VSS_PAD_P$83") (pintype "bidirectional"))
      (node (ref "U1") (pin "P$84") (pinfunction "VSS_PAD_P$84") (pintype "bidirectional"))
      (node (ref "U1") (pin "P$85") (pinfunction "VSS_PAD_P$85") (pintype "bidirectional"))
      (node (ref "U1") (pin "P$86") (pinfunction "VSS_PAD_P$86") (pintype "bidirectional"))
      (node (ref "U1") (pin "P$87") (pinfunction "VSS_PAD_P$87") (pintype "bidirectional"))
      (node (ref "U1") (pin "P$88") (pinfunction "VSS_PAD_P$88") (pintype "bidirectional"))
      (node (ref "U1") (pin "P$89") (pinfunction "VSS_PAD_P$89") (pintype "bidirectional"))
      (node (ref "U1") (pin "P$90") (pinfunction "VSS_PAD_P$90") (pintype "bidirectional"))
      (node (ref "U1") (pin "P$B7") (pinfunction "VSS_P$B7") (pintype "power_in"))
      (node (ref "U1") (pin "P$F23") (pinfunction "VSS_PA_P$F23") (pintype "bidirectional"))
      (node (ref "U3") (pin "1") (pinfunction "CTG_1") (pintype "power_in"))
      (node (ref "U3") (pin "4") (pinfunction "GND_4") (pintype "power_in"))
      (node (ref "U3") (pin "6") (pinfunction "QSTRT_6") (pintype "input"))
      (node (ref "U3") (pin "9") (pinfunction "EP_9") (pintype "power_in"))
      (node (ref "X1") (pin "2") (pinfunction "2_2") (pintype "passive"))
      (node (ref "X1") (pin "4") (pinfunction "4_4") (pintype "passive"))
    )
    (net (code "17") (name "HAPTIC_EN") (class "Default")
      (node (ref "IC2") (pin "A1") (pinfunction "EN_A1") (pintype "bidirectional"))
      (node (ref "U1") (pin "P$U1") (pinfunction "P0.12_P$U1") (pintype "bidirectional"))
    )
    (net (code "18") (name "IMU_INT1") (class "Default")
      (node (ref "IC3") (pin "5") (pinfunction "INT1_5") (pintype "bidirectional"))
      (node (ref "U1") (pin "P$N1") (pinfunction "P0.08_P$N1") (pintype "bidirectional"))
    )
    (net (code "19") (name "IMU_INT2") (class "Default")
      (node (ref "IC3") (pin "6") (pinfunction "INT2_6") (pintype "bidirectional"))
      (node (ref "U1") (pin "P$P2") (pinfunction "P1.08_P$P2") (pintype "bidirectional"))
    )
    (net (code "20") (name "LX1") (class "Default")
      (node (ref "IC9") (pin "B2") (pinfunction "SW1_1_B2") (pintype "bidirectional"))
      (node (ref "IC9") (pin "B3") (pinfunction "SW1_2_B3") (pintype "bidirectional"))
      (node (ref "L7") (pin "1") (pinfunction "1_1") (pintype "bidirectional"))
    )
    (net (code "21") (name "LX2") (class "Default")
      (node (ref "IC9") (pin "D2") (pinfunction "SW2_1_D2") (pintype "bidirectional"))
      (node (ref "IC9") (pin "D3") (pinfunction "SW2_2_D3") (pintype "bidirectional"))
      (node (ref "L7") (pin "2") (pinfunction "2_2") (pintype "bidirectional"))
    )
    (net (code "22") (name "MOSI") (class "Default")
      (node (ref "J1") (pin "14") (pinfunction "14_14") (pintype "bidirectional"))
      (node (ref "U1") (pin "P$B13") (pinfunction "P0.03/AIN1_P$B13") (pintype "bidirectional"))
    )
    (net (code "23") (name "Net-(ANT1-FEED)") (class "Default")
      (node (ref "ANT1") (pin "1") (pinfunction "FEED_1") (pintype "input"))
      (node (ref "C22") (pin "1") (pinfunction "1_1") (pintype "passive"))
      (node (ref "C4") (pin "1") (pinfunction "1_1") (pintype "passive"))
      (node (ref "L1") (pin "2") (pinfunction "2_2") (pintype "passive"))
    )
    (net (code "24") (name "Net-(D2-K)") (class "Default")
      (node (ref "C2-EP-DR") (pin "1") (pinfunction "1_1") (pintype "passive"))
      (node (ref "D2") (pin "1") (pinfunction "K_1") (pintype "bidirectional"))
      (node (ref "D4") (pin "2") (pinfunction "A_2") (pintype "bidirectional"))
    )
    (net (code "25") (name "Net-(D5-A)") (class "Default")
      (node (ref "C2-EP-DR") (pin "2") (pinfunction "2_2") (pintype "passive"))
      (node (ref "D5") (pin "2") (pinfunction "A_2") (pintype "bidirectional"))
      (node (ref "L5") (pin "1") (pinfunction "1_1") (pintype "passive"))
      (node (ref "Q3") (pin "3") (pinfunction "D_3") (pintype "bidirectional"))
    )
    (net (code "26") (name "Net-(EPD_C1-Pad2)") (class "Default")
      (node (ref "EPD_C1") (pin "2") (pinfunction "2_2") (pintype "passive"))
      (node (ref "J1") (pin "5") (pinfunction "5_5") (pintype "bidirectional"))
    )
    (net (code "27") (name "Net-(EPD_C2-Pad2)") (class "Default")
      (node (ref "EPD_C2") (pin "2") (pinfunction "2_2") (pintype "passive"))
      (node (ref "J1") (pin "4") (pinfunction "4_4") (pintype "bidirectional"))
    )
    (net (code "28") (name "Net-(EPD_C6-Pad2)") (class "Default")
      (node (ref "EPD_C6") (pin "2") (pinfunction "2_2") (pintype "passive"))
      (node (ref "J1") (pin "18") (pinfunction "18_18") (pintype "bidirectional"))
    )
    (net (code "29") (name "Net-(EPD_C7-Pad2)") (class "Default")
      (node (ref "EPD_C7") (pin "2") (pinfunction "2_2") (pintype "passive"))
      (node (ref "J1") (pin "19") (pinfunction "19_19") (pintype "bidirectional"))
    )
    (net (code "30") (name "Net-(EPD_C8-Pad2)") (class "Default")
      (node (ref "EPD_C8") (pin "2") (pinfunction "2_2") (pintype "passive"))
      (node (ref "J1") (pin "20") (pinfunction "20_20") (pintype "bidirectional"))
    )
    (net (code "31") (name "Net-(EPD_C10-Pad2)") (class "Default")
      (node (ref "EPD_C10") (pin "2") (pinfunction "2_2") (pintype "passive"))
      (node (ref "J1") (pin "22") (pinfunction "22_22") (pintype "bidirectional"))
    )
    (net (code "32") (name "Net-(EPD_C12-Pad2)") (class "Default")
      (node (ref "EPD_C12") (pin "2") (pinfunction "2_2") (pintype "passive"))
      (node (ref "J1") (pin "24") (pinfunction "24_24") (pintype "bidirectional"))
    )
    (net (code "33") (name "Net-(IC1-TS{slash}MR)") (class "Default")
      (node (ref "IC1") (pin "D1") (pinfunction "TS/MR_D1") (pintype "bidirectional"))
      (node (ref "R9") (pin "2") (pinfunction "2_2") (pintype "bidirectional"))
    )
    (net (code "34") (name "Net-(IC2-REG)") (class "Default")
      (node (ref "C32") (pin "1") (pinfunction "1_1") (pintype "passive"))
      (node (ref "IC2") (pin "A2") (pinfunction "REG_A2") (pintype "bidirectional"))
    )
    (net (code "35") (name "Net-(IC3-SDO)") (class "Default")
      (node (ref "IC3") (pin "1") (pinfunction "SDO_1") (pintype "bidirectional"))
      (node (ref "R3") (pin "1") (pinfunction "1_1") (pintype "bidirectional"))
    )
    (net (code "36") (name "Net-(IC9-SCL)") (class "Default")
      (node (ref "IC9") (pin "D1") (pinfunction "SCL_D1") (pintype "bidirectional"))
      (node (ref "R4") (pin "1") (pinfunction "1_1") (pintype "bidirectional"))
    )
    (net (code "37") (name "Net-(IC9-SDA)") (class "Default")
      (node (ref "IC9") (pin "E1") (pinfunction "SDA_E1") (pintype "bidirectional"))
      (node (ref "R2") (pin "1") (pinfunction "1_1") (pintype "bidirectional"))
    )
    (net (code "38") (name "Net-(J4-CC1)") (class "Default")
      (node (ref "J4") (pin "A5") (pinfunction "CC1_A5") (pintype "bidirectional"))
      (node (ref "R1_USB") (pin "2") (pinfunction "2_2") (pintype "bidirectional"))
    )
    (net (code "39") (name "Net-(J4-CC2)") (class "Default")
      (node (ref "J4") (pin "B5") (pinfunction "CC2_B5") (pintype "bidirectional"))
      (node (ref "R2_USB") (pin "1") (pinfunction "1_1") (pintype "bidirectional"))
    )
    (net (code "40") (name "Net-(L2-Pad2)") (class "Default")
      (node (ref "L2") (pin "2") (pinfunction "2_2") (pintype "passive"))
      (node (ref "L3") (pin "1") (pinfunction "1_1") (pintype "passive"))
    )
    (net (code "41") (name "Net-(R1_EP_DR-Pad1)") (class "Default")
      (node (ref "R1_EP_DR") (pin "1") (pinfunction "1_1") (pintype "bidirectional"))
      (node (ref "R_TYPE_SEL") (pin "2") (pinfunction "2_2") (pintype "bidirectional"))
      (node (ref "SJ1") (pin "2") (pinfunction "2_2") (pintype "passive"))
    )
    (net (code "42") (name "Net-(U1-ANT)") (class "Default")
      (node (ref "C3") (pin "1") (pinfunction "1_1") (pintype "passive"))
      (node (ref "L1") (pin "1") (pinfunction "1_1") (pintype "passive"))
      (node (ref "U1") (pin "P$H23") (pinfunction "ANT_P$H23") (pintype "bidirectional"))
    )
    (net (code "43") (name "Net-(U1-DCC)") (class "Default")
      (node (ref "L2") (pin "1") (pinfunction "1_1") (pintype "passive"))
      (node (ref "U1") (pin "P$B3") (pinfunction "DCC_P$B3") (pintype "output"))
    )
    (net (code "44") (name "Net-(U1-DEC1)") (class "Default")
      (node (ref "C5") (pin "1") (pinfunction "1_1") (pintype "passive"))
      (node (ref "U1") (pin "P$C1") (pinfunction "DEC1_P$C1") (pintype "power_in"))
    )
    (net (code "45") (name "Net-(U1-DEC2)") (class "Default")
      (node (ref "C13") (pin "1") (pinfunction "1_1") (pintype "passive"))
      (node (ref "U1") (pin "P$A18") (pinfunction "DEC2_P$A18") (pintype "bidirectional"))
    )
    (net (code "46") (name "Net-(U1-DEC3)") (class "Default")
      (node (ref "C11") (pin "1") (pinfunction "1_1") (pintype "passive"))
      (node (ref "U1") (pin "P$D23") (pinfunction "DEC3_P$D23") (pintype "bidirectional"))
    )
    (net (code "47") (name "Net-(U1-DEC3V3)") (class "Default")
      (node (ref "C20") (pin "1") (pinfunction "1_1") (pintype "passive"))
      (node (ref "U1") (pin "P$AC5") (pinfunction "DEC3V3_P$AC5") (pintype "bidirectional"))
    )
    (net (code "48") (name "Net-(U1-DEC5)") (class "Default")
      (node (ref "C9") (pin "1") (pinfunction "1_1") (pintype "passive"))
      (node (ref "U1") (pin "P$N24") (pinfunction "DEC5_P$N24") (pintype "bidirectional"))
    )
    (net (code "49") (name "Net-(U1-XC1)") (class "Default")
      (node (ref "C1") (pin "1") (pinfunction "1_1") (pintype "passive"))
      (node (ref "U1") (pin "P$B24") (pinfunction "XC1_P$B24") (pintype "input"))
      (node (ref "X1") (pin "1") (pinfunction "1_1") (pintype "passive"))
    )
    (net (code "50") (name "Net-(U1-XC2)") (class "Default")
      (node (ref "C2") (pin "1") (pinfunction "1_1") (pintype "passive"))
      (node (ref "U1") (pin "P$A23") (pinfunction "XC2_P$A23") (pintype "output"))
      (node (ref "X1") (pin "3") (pinfunction "3_3") (pintype "passive"))
    )
    (net (code "51") (name "OUT+") (class "Default")
      (node (ref "IC2") (pin "A3") (pinfunction "OUT+_A3") (pintype "bidirectional"))
      (node (ref "TP_OP") (pin "TP") (pinfunction "TP_TP") (pintype "input"))
    )
    (net (code "52") (name "OUT-") (class "Default")
      (node (ref "IC2") (pin "C3") (pinfunction "OUT-_C3") (pintype "bidirectional"))
      (node (ref "TP_ON") (pin "TP") (pinfunction "TP_TP") (pintype "input"))
    )
    (net (code "53") (name "P0.04") (class "Default")
      (node (ref "U1") (pin "P$J1") (pinfunction "P0.04/AIN2_P$J1") (pintype "bidirectional"))
    )
    (net (code "54") (name "P0.09") (class "Default")
      (node (ref "U1") (pin "P$L24") (pinfunction "P0.09/NFC1_P$L24") (pintype "bidirectional"))
    )
    (net (code "55") (name "P0.13") (class "Default")
      (node (ref "C30") (pin "1") (pinfunction "1_1") (pintype "passive"))
      (node (ref "R5") (pin "1") (pinfunction "1_1") (pintype "bidirectional"))
      (node (ref "SW_UP") (pin "2") (pinfunction "2_2") (pintype "passive"))
      (node (ref "U1") (pin "P$AD8") (pinfunction "P0.13_P$AD8") (pintype "bidirectional"))
    )
    (net (code "56") (name "P0.14") (class "Default")
      (node (ref "C31") (pin "1") (pinfunction "1_1") (pintype "passive"))
      (node (ref "R8") (pin "1") (pinfunction "1_1") (pintype "bidirectional"))
      (node (ref "SW_ENT") (pin "2") (pinfunction "2_2") (pintype "passive"))
      (node (ref "U1") (pin "P$AC9") (pinfunction "P0.14_P$AC9") (pintype "bidirectional"))
    )
    (net (code "57") (name "P0.19") (class "Default")
      (node (ref "U1") (pin "P$AC15") (pinfunction "P0.19_P$AC15") (pintype "bidirectional"))
    )
    (net (code "58") (name "P0.20") (class "Default")
      (node (ref "U1") (pin "P$AD16") (pinfunction "P0.20_P$AD16") (pintype "bidirectional"))
    )
    (net (code "59") (name "P0.21") (class "Default")
      (node (ref "U1") (pin "P$AC17") (pinfunction "P0.21_P$AC17") (pintype "bidirectional"))
    )
    (net (code "60") (name "P0.22") (class "Default")
      (node (ref "U1") (pin "P$AD18") (pinfunction "P0.22_P$AD18") (pintype "bidirectional"))
    )
    (net (code "61") (name "P0.23") (class "Default")
      (node (ref "U1") (pin "P$AC19") (pinfunction "P0.23_P$AC19") (pintype "bidirectional"))
    )
    (net (code "62") (name "P0.24") (class "Default")
      (node (ref "U1") (pin "P$AD20") (pinfunction "P0.24_P$AD20") (pintype "bidirectional"))
    )
    (net (code "63") (name "P0.25") (class "Default")
      (node (ref "U1") (pin "P$AC21") (pinfunction "P0.25_P$AC21") (pintype "bidirectional"))
    )
    (net (code "64") (name "P0.26") (class "Default")
      (node (ref "U1") (pin "P$G1") (pinfunction "P0.26_P$G1") (pintype "bidirectional"))
    )
    (net (code "65") (name "P0.27") (class "Default")
      (node (ref "U1") (pin "P$H2") (pinfunction "P0.27_P$H2") (pintype "bidirectional"))
    )
    (net (code "66") (name "P0.28") (class "Default")
      (node (ref "U1") (pin "P$B11") (pinfunction "P0.28/AIN4_P$B11") (pintype "bidirectional"))
    )
    (net (code "67") (name "P0.29") (class "Default")
      (node (ref "U1") (pin "P$A10") (pinfunction "P0.29/AIN5_P$A10") (pintype "bidirectional"))
    )
    (net (code "68") (name "P0.30") (class "Default")
      (node (ref "U1") (pin "P$B9") (pinfunction "P0.30/AIN6_P$B9") (pintype "bidirectional"))
    )
    (net (code "69") (name "P0.31") (class "Default")
      (node (ref "U1") (pin "P$A8") (pinfunction "P0.31/AIN7_P$A8") (pintype "bidirectional"))
    )
    (net (code "70") (name "P1.01") (class "Default")
      (node (ref "DMG2305UX-7") (pin "1") (pinfunction "G_1") (pintype "bidirectional"))
      (node (ref "R_PWR_EPD") (pin "1") (pinfunction "1_1") (pintype "bidirectional"))
      (node (ref "U1") (pin "P$Y23") (pinfunction "P1.01_P$Y23") (pintype "bidirectional"))
    )
    (net (code "71") (name "P1.02") (class "Default")
      (node (ref "C29") (pin "1") (pinfunction "1_1") (pintype "passive"))
      (node (ref "R7") (pin "1") (pinfunction "1_1") (pintype "bidirectional"))
      (node (ref "SW_DN") (pin "2") (pinfunction "2_2") (pintype "passive"))
      (node (ref "U1") (pin "P$W24") (pinfunction "P1.02_P$W24") (pintype "bidirectional"))
    )
    (net (code "72") (name "P1.03") (class "Default")
      (node (ref "U1") (pin "P$V23") (pinfunction "P1.03_P$V23") (pintype "bidirectional"))
    )
    (net (code "73") (name "P1.04") (class "Default")
      (node (ref "U1") (pin "P$U24") (pinfunction "P1.04_P$U24") (pintype "bidirectional"))
    )
    (net (code "74") (name "P1.05") (class "Default")
      (node (ref "U1") (pin "P$T23") (pinfunction "P1.05_P$T23") (pintype "bidirectional"))
    )
    (net (code "75") (name "P1.06") (class "Default")
      (node (ref "U1") (pin "P$R24") (pinfunction "P1.06_P$R24") (pintype "bidirectional"))
    )
    (net (code "76") (name "P1.07") (class "Default")
      (node (ref "U1") (pin "P$P23") (pinfunction "P1.07_P$P23") (pintype "bidirectional"))
    )
    (net (code "77") (name "P1.09") (class "Default")
      (node (ref "U1") (pin "P$R1") (pinfunction "P1.09_P$R1") (pintype "bidirectional"))
    )
    (net (code "78") (name "P1.10") (class "Default")
      (node (ref "U1") (pin "P$A20") (pinfunction "P1.10_P$A20") (pintype "bidirectional"))
    )
    (net (code "79") (name "P1.11") (class "Default")
      (node (ref "U1") (pin "P$B19") (pinfunction "P1.11_P$B19") (pintype "bidirectional"))
    )
    (net (code "80") (name "P1.12") (class "Default")
      (node (ref "U1") (pin "P$B17") (pinfunction "P1.12_P$B17") (pintype "bidirectional"))
    )
    (net (code "81") (name "P1.13") (class "Default")
      (node (ref "U1") (pin "P$A16") (pinfunction "P1.13_P$A16") (pintype "bidirectional"))
    )
    (net (code "82") (name "P1.14") (class "Default")
      (node (ref "U1") (pin "P$B15") (pinfunction "P1.14_P$B15") (pintype "bidirectional"))
    )
    (net (code "83") (name "P1.15") (class "Default")
      (node (ref "U1") (pin "P$A14") (pinfunction "P1.15_P$A14") (pintype "bidirectional"))
    )
    (net (code "84") (name "PMIC_INT") (class "Default")
      (node (ref "IC1") (pin "A1") (pinfunction "~{INT}_A1") (pintype "bidirectional"))
      (node (ref "U1") (pin "P$T2") (pinfunction "P0.11_P$T2") (pintype "bidirectional"))
    )
    (net (code "85") (name "PREVGH") (class "Default")
      (node (ref "D5") (pin "1") (pinfunction "K_1") (pintype "bidirectional"))
      (node (ref "EPD_C9") (pin "2") (pinfunction "2_2") (pintype "passive"))
      (node (ref "J1") (pin "21") (pinfunction "21_21") (pintype "bidirectional"))
    )
    (net (code "86") (name "PREVGL") (class "Default")
      (node (ref "D2") (pin "2") (pinfunction "A_2") (pintype "bidirectional"))
      (node (ref "EPD_C11") (pin "2") (pinfunction "2_2") (pintype "passive"))
      (node (ref "J1") (pin "23") (pinfunction "23_23") (pintype "bidirectional"))
    )
    (net (code "87") (name "RESE") (class "Default")
      (node (ref "J1") (pin "3") (pinfunction "3_3") (pintype "bidirectional"))
      (node (ref "Q3") (pin "2") (pinfunction "S_2") (pintype "bidirectional"))
      (node (ref "R1_EP_DR") (pin "2") (pinfunction "2_2") (pintype "bidirectional"))
    )
    (net (code "88") (name "RESET") (class "Default")
      (node (ref "J5") (pin "6") (pinfunction "6_6") (pintype "bidirectional"))
      (node (ref "TP_RESET") (pin "TP") (pinfunction "TP_TP") (pintype "input"))
      (node (ref "U1") (pin "P$AC13") (pinfunction "P0.18/RESET_P$AC13") (pintype "bidirectional"))
    )
    (net (code "89") (name "SCK") (class "Default")
      (node (ref "J1") (pin "13") (pinfunction "13_13") (pintype "bidirectional"))
      (node (ref "U1") (pin "P$A12") (pinfunction "P0.02/AIN0_P$A12") (pintype "bidirectional"))
    )
    (net (code "90") (name "SCL") (class "Default")
      (node (ref "IC1") (pin "B1") (pinfunction "SCL_B1") (pintype "bidirectional"))
      (node (ref "IC2") (pin "C1") (pinfunction "SCL_C1") (pintype "bidirectional"))
      (node (ref "IC3") (pin "12") (pinfunction "SCX_12") (pintype "bidirectional"))
      (node (ref "R17") (pin "2") (pinfunction "2_2") (pintype "bidirectional"))
      (node (ref "R4") (pin "2") (pinfunction "2_2") (pintype "bidirectional"))
      (node (ref "TP_SCL") (pin "TP") (pinfunction "TP_TP") (pintype "input"))
      (node (ref "U1") (pin "P$M2") (pinfunction "P0.07_P$M2") (pintype "bidirectional"))
      (node (ref "U3") (pin "7") (pinfunction "SCL_7") (pintype "input"))
    )
    (net (code "91") (name "SDA") (class "Default")
      (node (ref "IC1") (pin "C1") (pinfunction "SDA_C1") (pintype "bidirectional"))
      (node (ref "IC2") (pin "B2") (pinfunction "SDA_B2") (pintype "bidirectional"))
      (node (ref "IC3") (pin "2") (pinfunction "SDX_2") (pintype "bidirectional"))
      (node (ref "R18") (pin "2") (pinfunction "2_2") (pintype "bidirectional"))
      (node (ref "R2") (pin "2") (pinfunction "2_2") (pintype "bidirectional"))
      (node (ref "TP_SDA") (pin "TP") (pinfunction "TP_TP") (pintype "input"))
      (node (ref "U1") (pin "P$L1") (pinfunction "P0.06_P$L1") (pintype "bidirectional"))
      (node (ref "U3") (pin "8") (pinfunction "SDA_8") (pintype "bidirectional"))
    )
    (net (code "92") (name "SWDCLK") (class "Default")
      (node (ref "J5") (pin "4") (pinfunction "4_4") (pintype "bidirectional"))
      (node (ref "TP_SWDCLK") (pin "TP") (pinfunction "TP_TP") (pintype "input"))
      (node (ref "U1") (pin "P$AA24") (pinfunction "SWDCLK_P$AA24") (pintype "input"))
    )
    (net (code "93") (name "SWDIO") (class "Default")
      (node (ref "J5") (pin "2") (pinfunction "2_2") (pintype "bidirectional"))
      (node (ref "TP_SWDIO") (pin "TP") (pinfunction "TP_TP") (pintype "input"))
      (node (ref "U1") (pin "P$AC24") (pinfunction "SWDIO_P$AC24") (pintype "bidirectional"))
    )
    (net (code "94") (name "SWO") (class "Default")
      (node (ref "TP_SWO") (pin "TP") (pinfunction "TP_TP") (pintype "input"))
      (node (ref "U1") (pin "P$AD22") (pinfunction "P1.00_P$AD22") (pintype "bidirectional"))
    )
    (net (code "95") (name "VBAT") (class "Default")
      (node (ref "C27") (pin "1") (pinfunction "1_1") (pintype "passive"))
      (node (ref "C37") (pin "1") (pinfunction "1_1") (pintype "passive"))
      (node (ref "IC1") (pin "C2") (pinfunction "BAT_C2") (pintype "bidirectional"))
      (node (ref "TP_VBAT") (pin "TP") (pinfunction "TP_TP") (pintype "input"))
      (node (ref "U3") (pin "2") (pinfunction "CELL_2") (pintype "power_in"))
      (node (ref "U3") (pin "3") (pinfunction "VDD_3") (pintype "power_in"))
    )
    (net (code "96") (name "VBUS") (class "Default")
      (node (ref "C21") (pin "1") (pinfunction "1_1") (pintype "passive"))
      (node (ref "C38") (pin "1") (pinfunction "1_1") (pintype "passive"))
      (node (ref "C42") (pin "1") (pinfunction "1_1") (pintype "passive"))
      (node (ref "C43") (pin "1") (pinfunction "1_1") (pintype "passive"))
      (node (ref "D3") (pin "5") (pinfunction "VBUS_5") (pintype "bidirectional"))
      (node (ref "IC1") (pin "A2") (pinfunction "IN_A2") (pintype "bidirectional"))
      (node (ref "J4") (pin "A4_B9") (pinfunction "VBUS_A4_B9") (pintype "power_in"))
      (node (ref "J4") (pin "A9_B4") (pinfunction "VBUS_A9_B4") (pintype "power_in"))
      (node (ref "U1") (pin "P$AD2") (pinfunction "VBUS_P$AD2") (pintype "power_in"))
    )
    (net (code "97") (name "VREG") (class "Default")
      (node (ref "C23") (pin "1") (pinfunction "1_1") (pintype "passive"))
      (node (ref "C24") (pin "2") (pinfunction "2_2") (pintype "passive"))
      (node (ref "C39") (pin "1") (pinfunction "1_1") (pintype "passive"))
      (node (ref "IC1") (pin "B2") (pinfunction "SYS_B2") (pintype "bidirectional"))
      (node (ref "IC9") (pin "A1") (pinfunction "EN_A1") (pintype "bidirectional"))
      (node (ref "IC9") (pin "A2") (pinfunction "VIN_1_A2") (pintype "bidirectional"))
      (node (ref "IC9") (pin "A3") (pinfunction "VIN_2_A3") (pintype "bidirectional"))
      (node (ref "TP_VREG") (pin "TP") (pinfunction "TP_TP") (pintype "input"))
    )
    (net (code "98") (name "unconnected-(ANT1-NC-Pad2)") (class "Default")
      (node (ref "ANT1") (pin "2") (pinfunction "NC_2") (pintype "no_connect"))
    )
    (net (code "99") (name "unconnected-(IC3-ASCL-Pad11)") (class "Default")
      (node (ref "IC3") (pin "11") (pinfunction "ASCL_11") (pintype "bidirectional"))
    )
    (net (code "100") (name "unconnected-(IC3-ASDA-Pad4)") (class "Default")
      (node (ref "IC3") (pin "4") (pinfunction "ASDA_4") (pintype "bidirectional"))
    )
    (net (code "101") (name "unconnected-(J1-Pad1)") (class "Default")
      (node (ref "J1") (pin "1") (pinfunction "1_1") (pintype "bidirectional"))
    )
    (net (code "102") (name "unconnected-(J1-Pad6)") (class "Default")
      (node (ref "J1") (pin "6") (pinfunction "6_6") (pintype "bidirectional"))
    )
    (net (code "103") (name "unconnected-(J1-Pad7)") (class "Default")
      (node (ref "J1") (pin "7") (pinfunction "7_7") (pintype "bidirectional"))
    )
    (net (code "104") (name "unconnected-(J4-SBU1-PadA8)") (class "Default")
      (node (ref "J4") (pin "A8") (pinfunction "SBU1_A8") (pintype "bidirectional"))
    )
    (net (code "105") (name "unconnected-(J4-SBU2-PadB8)") (class "Default")
      (node (ref "J4") (pin "B8") (pinfunction "SBU2_B8") (pintype "bidirectional"))
    )
    (net (code "106") (name "unconnected-(U1-DCCH-PadP$AB2)") (class "Default")
      (node (ref "U1") (pin "P$AB2") (pinfunction "DCCH_P$AB2") (pintype "bidirectional"))
    )
  )
)
